# G021Kng.net
KiCad netlist of a schematic drawn in EAGLE
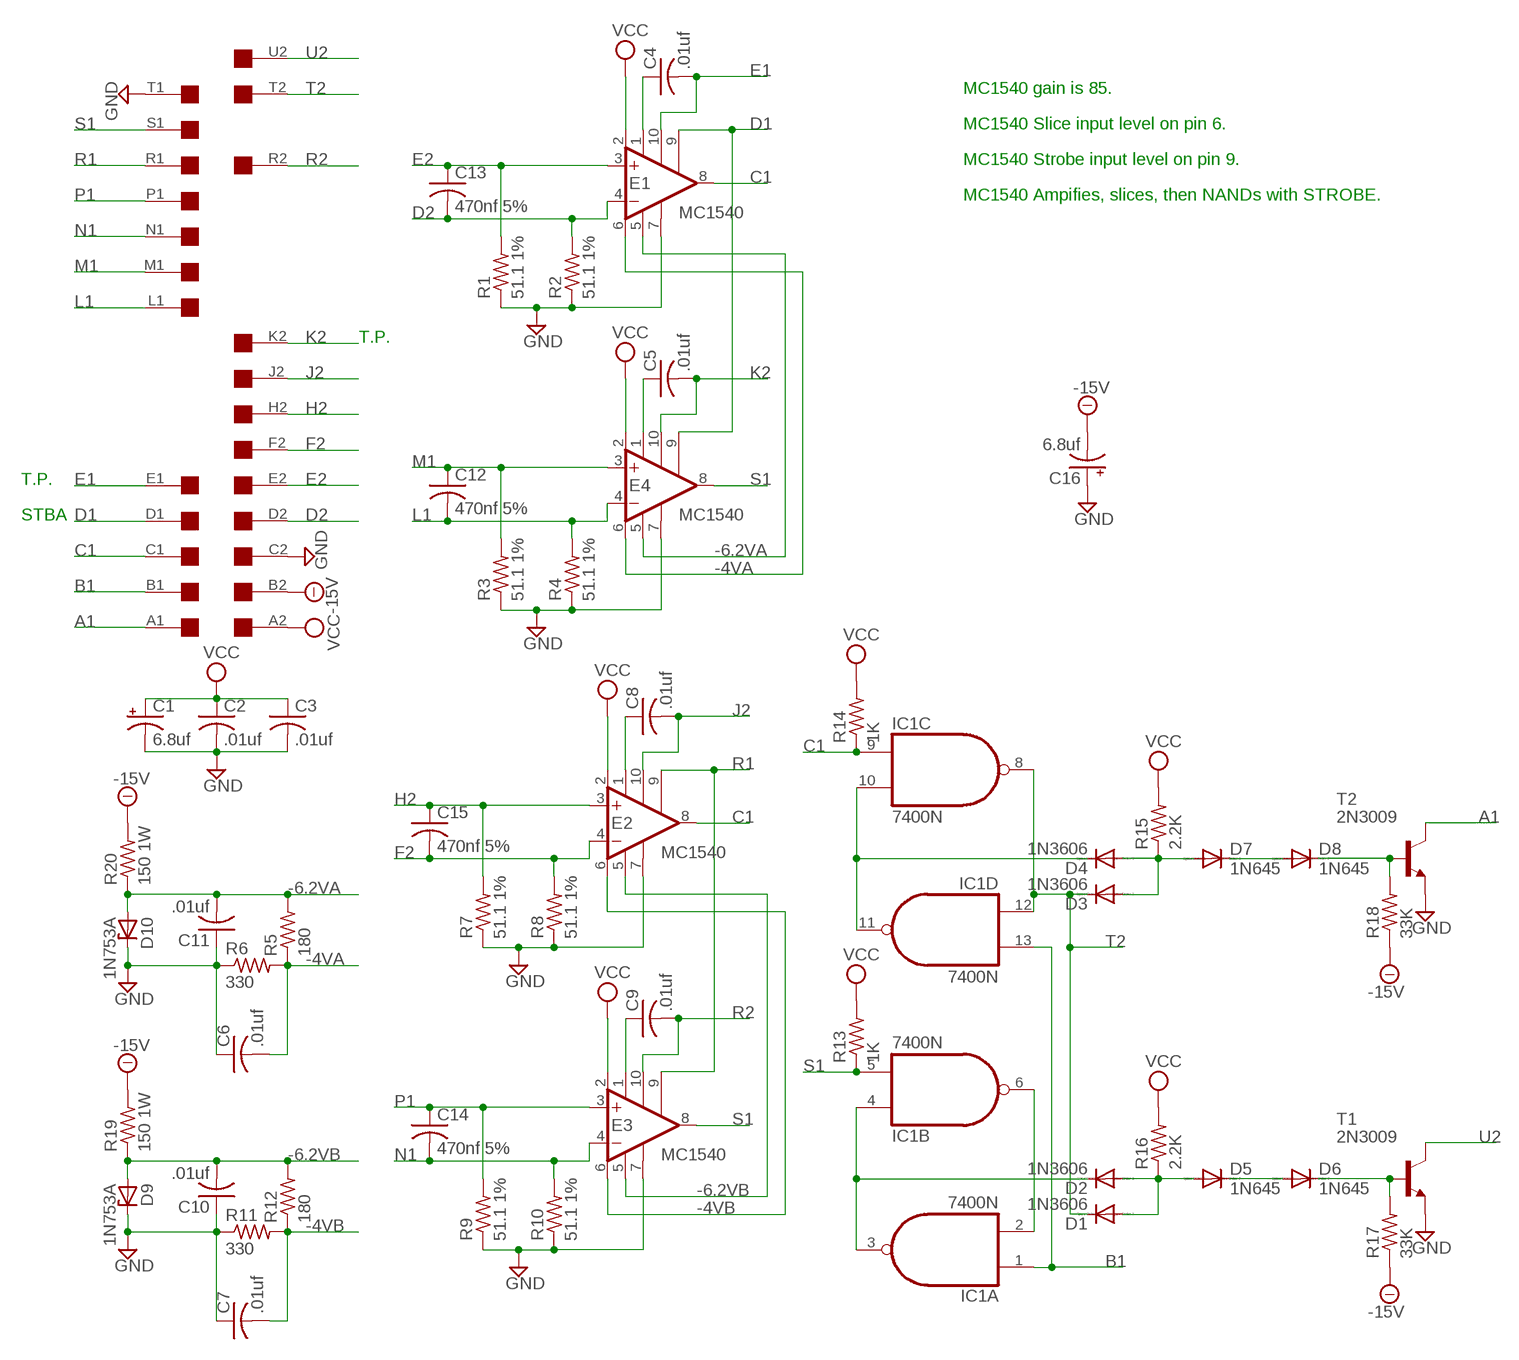
[diagram p0: schematic, sheet 1]

(export (version "E")
  (design (tool "Eeschema 10.0.6"))
  (components
    (comp (ref "C1")
      (value "6.8uf")
      (footprint "eagle-import:E22-6")
      (libsource (lib "eagle-import") (part "CPOL-USE22-6AXIAL"))
    )
    (comp (ref "C2")
      (value ".01uf")
      (footprint "eagle-import:C050-025X075")
      (libsource (lib "eagle-import") (part "C-US050-025X075"))
    )
    (comp (ref "C3")
      (value ".01uf")
      (footprint "eagle-import:C050-025X075")
      (libsource (lib "eagle-import") (part "C-US050-025X075"))
    )
    (comp (ref "C4")
      (value ".01uf")
      (footprint "eagle-import:C050-025X075")
      (libsource (lib "eagle-import") (part "C-US050-025X075"))
    )
    (comp (ref "C5")
      (value ".01uf")
      (footprint "eagle-import:C050-025X075")
      (libsource (lib "eagle-import") (part "C-US050-025X075"))
    )
    (comp (ref "C6")
      (value ".01uf")
      (footprint "eagle-import:C050-025X075")
      (libsource (lib "eagle-import") (part "C-US050-025X075"))
    )
    (comp (ref "C7")
      (value ".01uf")
      (footprint "eagle-import:C050-025X075")
      (libsource (lib "eagle-import") (part "C-US050-025X075"))
    )
    (comp (ref "C8")
      (value ".01uf")
      (footprint "eagle-import:C050-025X075")
      (libsource (lib "eagle-import") (part "C-US050-025X075"))
    )
    (comp (ref "C9")
      (value ".01uf")
      (footprint "eagle-import:C050-025X075")
      (libsource (lib "eagle-import") (part "C-US050-025X075"))
    )
    (comp (ref "C10")
      (value ".01uf")
      (footprint "eagle-import:C050-025X075")
      (libsource (lib "eagle-import") (part "C-US050-025X075"))
    )
    (comp (ref "C11")
      (value ".01uf")
      (footprint "eagle-import:C050-025X075")
      (libsource (lib "eagle-import") (part "C-US050-025X075"))
    )
    (comp (ref "C12")
      (value "470nf 5%")
      (footprint "eagle-import:C050-025X075")
      (libsource (lib "eagle-import") (part "C-US050-025X075"))
    )
    (comp (ref "C13")
      (value "470nf 5%")
      (footprint "eagle-import:C050-025X075")
      (libsource (lib "eagle-import") (part "C-US050-025X075"))
    )
    (comp (ref "C14")
      (value "470nf 5%")
      (footprint "eagle-import:C050-025X075")
      (libsource (lib "eagle-import") (part "C-US050-025X075"))
    )
    (comp (ref "C15")
      (value "470nf 5%")
      (footprint "eagle-import:C050-025X075")
      (libsource (lib "eagle-import") (part "C-US050-025X075"))
    )
    (comp (ref "C16")
      (value "6.8uf")
      (footprint "eagle-import:E22-6")
      (libsource (lib "eagle-import") (part "CPOL-USE22-6AXIAL"))
    )
    (comp (ref "D1")
      (value "1N3606")
      (footprint "eagle-import:DO35-10")
      (libsource (lib "eagle-import") (part "1N4148DO35-10"))
    )
    (comp (ref "D2")
      (value "1N3606")
      (footprint "eagle-import:DO35-10")
      (libsource (lib "eagle-import") (part "1N4148DO35-10"))
    )
    (comp (ref "D3")
      (value "1N3606")
      (footprint "eagle-import:DO35-10")
      (libsource (lib "eagle-import") (part "1N4148DO35-10"))
    )
    (comp (ref "D4")
      (value "1N3606")
      (footprint "eagle-import:DO35-10")
      (libsource (lib "eagle-import") (part "1N4148DO35-10"))
    )
    (comp (ref "D5")
      (value "1N645")
      (footprint "eagle-import:DO35-10")
      (libsource (lib "eagle-import") (part "1N4148DO35-10"))
    )
    (comp (ref "D6")
      (value "1N645")
      (footprint "eagle-import:DO35-10")
      (libsource (lib "eagle-import") (part "1N4148DO35-10"))
    )
    (comp (ref "D7")
      (value "1N645")
      (footprint "eagle-import:DO35-10")
      (libsource (lib "eagle-import") (part "1N4148DO35-10"))
    )
    (comp (ref "D8")
      (value "1N645")
      (footprint "eagle-import:DO35-10")
      (libsource (lib "eagle-import") (part "1N4148DO35-10"))
    )
    (comp (ref "D9")
      (value "1N753A")
      (footprint "eagle-import:F126Z10")
      (libsource (lib "eagle-import") (part "ZENER-DIODEF126-10"))
    )
    (comp (ref "D10")
      (value "1N753A")
      (footprint "eagle-import:F126Z10")
      (libsource (lib "eagle-import") (part "ZENER-DIODEF126-10"))
    )
    (comp (ref "E1")
      (value "MC1540")
      (footprint "eagle-import:602B")
      (libsource (lib "eagle-import") (part "MC1540G"))
    )
    (comp (ref "E2")
      (value "MC1540")
      (footprint "eagle-import:602B")
      (libsource (lib "eagle-import") (part "MC1540G"))
    )
    (comp (ref "E3")
      (value "MC1540")
      (footprint "eagle-import:602B")
      (libsource (lib "eagle-import") (part "MC1540G"))
    )
    (comp (ref "E4")
      (value "MC1540")
      (footprint "eagle-import:602B")
      (libsource (lib "eagle-import") (part "MC1540G"))
    )
    (comp (ref "EDGE")
      (value "EDGE-2ECONO")
      (footprint "eagle-import:ECONOSINGLE")
      (libsource (lib "eagle-import") (part "EDGE-2ECONO"))
    )
    (comp (ref "IC1")
      (value "7400N")
      (footprint "eagle-import:DIL14")
      (libsource (lib "eagle-import") (part "7400N"))
    )
    (comp (ref "R1")
      (value "51.1 1%")
      (footprint "eagle-import:0207_10")
      (libsource (lib "eagle-import") (part "R-US_0207/10"))
    )
    (comp (ref "R2")
      (value "51.1 1%")
      (footprint "eagle-import:0207_10")
      (libsource (lib "eagle-import") (part "R-US_0207/10"))
    )
    (comp (ref "R3")
      (value "51.1 1%")
      (footprint "eagle-import:0207_10")
      (libsource (lib "eagle-import") (part "R-US_0207/10"))
    )
    (comp (ref "R4")
      (value "51.1 1%")
      (footprint "eagle-import:0207_10")
      (libsource (lib "eagle-import") (part "R-US_0207/10"))
    )
    (comp (ref "R5")
      (value "180")
      (footprint "eagle-import:0207_10")
      (libsource (lib "eagle-import") (part "R-US_0207/10"))
    )
    (comp (ref "R6")
      (value "330")
      (footprint "eagle-import:0207_10")
      (libsource (lib "eagle-import") (part "R-US_0207/10"))
    )
    (comp (ref "R7")
      (value "51.1 1%")
      (footprint "eagle-import:0207_10")
      (libsource (lib "eagle-import") (part "R-US_0207/10"))
    )
    (comp (ref "R8")
      (value "51.1 1%")
      (footprint "eagle-import:0207_10")
      (libsource (lib "eagle-import") (part "R-US_0207/10"))
    )
    (comp (ref "R9")
      (value "51.1 1%")
      (footprint "eagle-import:0207_10")
      (libsource (lib "eagle-import") (part "R-US_0207/10"))
    )
    (comp (ref "R10")
      (value "51.1 1%")
      (footprint "eagle-import:0207_10")
      (libsource (lib "eagle-import") (part "R-US_0207/10"))
    )
    (comp (ref "R11")
      (value "330")
      (footprint "eagle-import:0207_10")
      (libsource (lib "eagle-import") (part "R-US_0207/10"))
    )
    (comp (ref "R12")
      (value "180")
      (footprint "eagle-import:0207_10")
      (libsource (lib "eagle-import") (part "R-US_0207/10"))
    )
    (comp (ref "R13")
      (value "1K")
      (footprint "eagle-import:0207_10")
      (libsource (lib "eagle-import") (part "R-US_0207/10"))
    )
    (comp (ref "R14")
      (value "1K")
      (footprint "eagle-import:0207_10")
      (libsource (lib "eagle-import") (part "R-US_0207/10"))
    )
    (comp (ref "R15")
      (value "2.2K")
      (footprint "eagle-import:0207_10")
      (libsource (lib "eagle-import") (part "R-US_0207/10"))
    )
    (comp (ref "R16")
      (value "2.2K")
      (footprint "eagle-import:0207_10")
      (libsource (lib "eagle-import") (part "R-US_0207/10"))
    )
    (comp (ref "R17")
      (value "33K")
      (footprint "eagle-import:0207_10")
      (libsource (lib "eagle-import") (part "R-US_0207/10"))
    )
    (comp (ref "R18")
      (value "33K")
      (footprint "eagle-import:0207_10")
      (libsource (lib "eagle-import") (part "R-US_0207/10"))
    )
    (comp (ref "R19")
      (value "150 1W")
      (footprint "eagle-import:0414_15")
      (libsource (lib "eagle-import") (part "R-US_0414/15"))
    )
    (comp (ref "R20")
      (value "150 1W")
      (footprint "eagle-import:0414_15")
      (libsource (lib "eagle-import") (part "R-US_0414/15"))
    )
    (comp (ref "T1")
      (value "2N3009")
      (footprint "eagle-import:TO92")
      (libsource (lib "eagle-import") (part "2N3565"))
    )
    (comp (ref "T2")
      (value "2N3009")
      (footprint "eagle-import:TO92")
      (libsource (lib "eagle-import") (part "2N3565"))
    )
  )
  (nets
    (net (code "1") (name "-15V") (class "Default")
      (node (ref "C16") (pin "-") (pinfunction "-_-") (pintype "passive"))
      (node (ref "EDGE") (pin "B2") (pinfunction "1_B2") (pintype "bidirectional"))
      (node (ref "R17") (pin "1") (pinfunction "1_1") (pintype "passive"))
      (node (ref "R18") (pin "1") (pinfunction "1_1") (pintype "passive"))
      (node (ref "R19") (pin "2") (pinfunction "2_2") (pintype "passive"))
      (node (ref "R20") (pin "2") (pinfunction "2_2") (pintype "passive"))
    )
    (net (code "2") (name "/-4VA") (class "Default")
      (node (ref "C6") (pin "2") (pinfunction "2_2") (pintype "passive"))
      (node (ref "E1") (pin "6") (pinfunction "SLICE_6") (pintype "bidirectional"))
      (node (ref "E4") (pin "6") (pinfunction "SLICE_6") (pintype "bidirectional"))
      (node (ref "R5") (pin "1") (pinfunction "1_1") (pintype "passive"))
      (node (ref "R6") (pin "2") (pinfunction "2_2") (pintype "passive"))
    )
    (net (code "3") (name "/-4VB") (class "Default")
      (node (ref "C7") (pin "2") (pinfunction "2_2") (pintype "passive"))
      (node (ref "E2") (pin "6") (pinfunction "SLICE_6") (pintype "bidirectional"))
      (node (ref "E3") (pin "6") (pinfunction "SLICE_6") (pintype "bidirectional"))
      (node (ref "R11") (pin "2") (pinfunction "2_2") (pintype "passive"))
      (node (ref "R12") (pin "1") (pinfunction "1_1") (pintype "passive"))
    )
    (net (code "4") (name "/-6.2VA") (class "Default")
      (node (ref "C11") (pin "2") (pinfunction "2_2") (pintype "passive"))
      (node (ref "D10") (pin "A") (pinfunction "A_A") (pintype "passive"))
      (node (ref "E1") (pin "5") (pinfunction "V-_5") (pintype "power_in"))
      (node (ref "E4") (pin "5") (pinfunction "V-_5") (pintype "power_in"))
      (node (ref "R20") (pin "1") (pinfunction "1_1") (pintype "passive"))
      (node (ref "R5") (pin "2") (pinfunction "2_2") (pintype "passive"))
    )
    (net (code "5") (name "/-6.2VB") (class "Default")
      (node (ref "C10") (pin "2") (pinfunction "2_2") (pintype "passive"))
      (node (ref "D9") (pin "A") (pinfunction "A_A") (pintype "passive"))
      (node (ref "E2") (pin "5") (pinfunction "V-_5") (pintype "power_in"))
      (node (ref "E3") (pin "5") (pinfunction "V-_5") (pintype "power_in"))
      (node (ref "R12") (pin "2") (pinfunction "2_2") (pintype "passive"))
      (node (ref "R19") (pin "1") (pinfunction "1_1") (pintype "passive"))
    )
    (net (code "6") (name "/A1") (class "Default")
      (node (ref "EDGE") (pin "A1") (pinfunction "1_A1") (pintype "bidirectional"))
      (node (ref "T2") (pin "1") (pinfunction "C_1") (pintype "passive"))
    )
    (net (code "7") (name "/B1") (class "Default")
      (node (ref "EDGE") (pin "B1") (pinfunction "1_B1") (pintype "bidirectional"))
      (node (ref "IC1") (pin "1") (pinfunction "I0_1") (pintype "input"))
      (node (ref "IC1") (pin "13") (pinfunction "I1_13") (pintype "input"))
    )
    (net (code "8") (name "/C1") (class "Default")
      (node (ref "E1") (pin "8") (pinfunction "OUT_8") (pintype "open_collector"))
      (node (ref "E2") (pin "8") (pinfunction "OUT_8") (pintype "open_collector"))
      (node (ref "EDGE") (pin "C1") (pinfunction "1_C1") (pintype "bidirectional"))
      (node (ref "IC1") (pin "9") (pinfunction "I0_9") (pintype "input"))
      (node (ref "R14") (pin "1") (pinfunction "1_1") (pintype "passive"))
    )
    (net (code "9") (name "/D1") (class "Default")
      (node (ref "E1") (pin "9") (pinfunction "ISTROBE_9") (pintype "passive"))
      (node (ref "E4") (pin "9") (pinfunction "ISTROBE_9") (pintype "passive"))
      (node (ref "EDGE") (pin "D1") (pinfunction "1_D1") (pintype "bidirectional"))
    )
    (net (code "10") (name "/D2") (class "Default")
      (node (ref "C13") (pin "2") (pinfunction "2_2") (pintype "passive"))
      (node (ref "E1") (pin "4") (pinfunction "-IN_4") (pintype "input"))
      (node (ref "EDGE") (pin "D2") (pinfunction "1_D2") (pintype "bidirectional"))
      (node (ref "R2") (pin "2") (pinfunction "2_2") (pintype "passive"))
    )
    (net (code "11") (name "/E1") (class "Default")
      (node (ref "C4") (pin "2") (pinfunction "2_2") (pintype "passive"))
      (node (ref "E1") (pin "10") (pinfunction "CEXTB_10") (pintype "passive"))
      (node (ref "EDGE") (pin "E1") (pinfunction "1_E1") (pintype "bidirectional"))
    )
    (net (code "12") (name "/E2") (class "Default")
      (node (ref "C13") (pin "1") (pinfunction "1_1") (pintype "passive"))
      (node (ref "E1") (pin "3") (pinfunction "+IN_3") (pintype "input"))
      (node (ref "EDGE") (pin "E2") (pinfunction "1_E2") (pintype "bidirectional"))
      (node (ref "R1") (pin "2") (pinfunction "2_2") (pintype "passive"))
    )
    (net (code "13") (name "/F2") (class "Default")
      (node (ref "C15") (pin "2") (pinfunction "2_2") (pintype "passive"))
      (node (ref "E2") (pin "4") (pinfunction "-IN_4") (pintype "input"))
      (node (ref "EDGE") (pin "F2") (pinfunction "1_F2") (pintype "bidirectional"))
      (node (ref "R8") (pin "2") (pinfunction "2_2") (pintype "passive"))
    )
    (net (code "14") (name "/H2") (class "Default")
      (node (ref "C15") (pin "1") (pinfunction "1_1") (pintype "passive"))
      (node (ref "E2") (pin "3") (pinfunction "+IN_3") (pintype "input"))
      (node (ref "EDGE") (pin "H2") (pinfunction "1_H2") (pintype "bidirectional"))
      (node (ref "R7") (pin "2") (pinfunction "2_2") (pintype "passive"))
    )
    (net (code "15") (name "/J2") (class "Default")
      (node (ref "C8") (pin "2") (pinfunction "2_2") (pintype "passive"))
      (node (ref "E2") (pin "10") (pinfunction "CEXTB_10") (pintype "passive"))
      (node (ref "EDGE") (pin "J2") (pinfunction "1_J2") (pintype "bidirectional"))
    )
    (net (code "16") (name "/K2") (class "Default")
      (node (ref "C5") (pin "2") (pinfunction "2_2") (pintype "passive"))
      (node (ref "E4") (pin "10") (pinfunction "CEXTB_10") (pintype "passive"))
      (node (ref "EDGE") (pin "K2") (pinfunction "1_K2") (pintype "bidirectional"))
    )
    (net (code "17") (name "/L1") (class "Default")
      (node (ref "C12") (pin "2") (pinfunction "2_2") (pintype "passive"))
      (node (ref "E4") (pin "4") (pinfunction "-IN_4") (pintype "input"))
      (node (ref "EDGE") (pin "L1") (pinfunction "1_L1") (pintype "bidirectional"))
      (node (ref "R4") (pin "2") (pinfunction "2_2") (pintype "passive"))
    )
    (net (code "18") (name "/M1") (class "Default")
      (node (ref "C12") (pin "1") (pinfunction "1_1") (pintype "passive"))
      (node (ref "E4") (pin "3") (pinfunction "+IN_3") (pintype "input"))
      (node (ref "EDGE") (pin "M1") (pinfunction "1_M1") (pintype "bidirectional"))
      (node (ref "R3") (pin "2") (pinfunction "2_2") (pintype "passive"))
    )
    (net (code "19") (name "/N1") (class "Default")
      (node (ref "C14") (pin "2") (pinfunction "2_2") (pintype "passive"))
      (node (ref "E3") (pin "4") (pinfunction "-IN_4") (pintype "input"))
      (node (ref "EDGE") (pin "N1") (pinfunction "1_N1") (pintype "bidirectional"))
      (node (ref "R10") (pin "2") (pinfunction "2_2") (pintype "passive"))
    )
    (net (code "20") (name "/P1") (class "Default")
      (node (ref "C14") (pin "1") (pinfunction "1_1") (pintype "passive"))
      (node (ref "E3") (pin "3") (pinfunction "+IN_3") (pintype "input"))
      (node (ref "EDGE") (pin "P1") (pinfunction "1_P1") (pintype "bidirectional"))
      (node (ref "R9") (pin "2") (pinfunction "2_2") (pintype "passive"))
    )
    (net (code "21") (name "/R1") (class "Default")
      (node (ref "E2") (pin "9") (pinfunction "ISTROBE_9") (pintype "passive"))
      (node (ref "E3") (pin "9") (pinfunction "ISTROBE_9") (pintype "passive"))
      (node (ref "EDGE") (pin "R1") (pinfunction "1_R1") (pintype "bidirectional"))
    )
    (net (code "22") (name "/R2") (class "Default")
      (node (ref "C9") (pin "2") (pinfunction "2_2") (pintype "passive"))
      (node (ref "E3") (pin "10") (pinfunction "CEXTB_10") (pintype "passive"))
      (node (ref "EDGE") (pin "R2") (pinfunction "1_R2") (pintype "bidirectional"))
    )
    (net (code "23") (name "/S1") (class "Default")
      (node (ref "E3") (pin "8") (pinfunction "OUT_8") (pintype "open_collector"))
      (node (ref "E4") (pin "8") (pinfunction "OUT_8") (pintype "open_collector"))
      (node (ref "EDGE") (pin "S1") (pinfunction "1_S1") (pintype "bidirectional"))
      (node (ref "IC1") (pin "5") (pinfunction "I1_5") (pintype "input"))
      (node (ref "R13") (pin "1") (pinfunction "1_1") (pintype "passive"))
    )
    (net (code "24") (name "/T2") (class "Default")
      (node (ref "D1") (pin "C") (pinfunction "C_C") (pintype "passive"))
      (node (ref "D3") (pin "C") (pinfunction "C_C") (pintype "passive"))
      (node (ref "EDGE") (pin "T2") (pinfunction "1_T2") (pintype "bidirectional"))
      (node (ref "IC1") (pin "12") (pinfunction "I0_12") (pintype "input"))
      (node (ref "IC1") (pin "8") (pinfunction "O_8") (pintype "output"))
    )
    (net (code "25") (name "/U2") (class "Default")
      (node (ref "EDGE") (pin "U2") (pinfunction "1_U2") (pintype "bidirectional"))
      (node (ref "T1") (pin "1") (pinfunction "C_1") (pintype "passive"))
    )
    (net (code "26") (name "GND") (class "Default")
      (node (ref "C1") (pin "-") (pinfunction "-_-") (pintype "passive"))
      (node (ref "C10") (pin "1") (pinfunction "1_1") (pintype "passive"))
      (node (ref "C11") (pin "1") (pinfunction "1_1") (pintype "passive"))
      (node (ref "C16") (pin "+") (pinfunction "+_+") (pintype "passive"))
      (node (ref "C2") (pin "2") (pinfunction "2_2") (pintype "passive"))
      (node (ref "C3") (pin "2") (pinfunction "2_2") (pintype "passive"))
      (node (ref "C6") (pin "1") (pinfunction "1_1") (pintype "passive"))
      (node (ref "C7") (pin "1") (pinfunction "1_1") (pintype "passive"))
      (node (ref "D10") (pin "C") (pinfunction "C_C") (pintype "passive"))
      (node (ref "D9") (pin "C") (pinfunction "C_C") (pintype "passive"))
      (node (ref "E1") (pin "7") (pinfunction "GND_7") (pintype "power_in"))
      (node (ref "E2") (pin "7") (pinfunction "GND_7") (pintype "power_in"))
      (node (ref "E3") (pin "7") (pinfunction "GND_7") (pintype "power_in"))
      (node (ref "E4") (pin "7") (pinfunction "GND_7") (pintype "power_in"))
      (node (ref "EDGE") (pin "C2") (pinfunction "1_C2") (pintype "bidirectional"))
      (node (ref "EDGE") (pin "T1") (pinfunction "1_T1") (pintype "bidirectional"))
      (node (ref "R1") (pin "1") (pinfunction "1_1") (pintype "passive"))
      (node (ref "R10") (pin "1") (pinfunction "1_1") (pintype "passive"))
      (node (ref "R11") (pin "1") (pinfunction "1_1") (pintype "passive"))
      (node (ref "R2") (pin "1") (pinfunction "1_1") (pintype "passive"))
      (node (ref "R3") (pin "1") (pinfunction "1_1") (pintype "passive"))
      (node (ref "R4") (pin "1") (pinfunction "1_1") (pintype "passive"))
      (node (ref "R6") (pin "1") (pinfunction "1_1") (pintype "passive"))
      (node (ref "R7") (pin "1") (pinfunction "1_1") (pintype "passive"))
      (node (ref "R8") (pin "1") (pinfunction "1_1") (pintype "passive"))
      (node (ref "R9") (pin "1") (pinfunction "1_1") (pintype "passive"))
      (node (ref "T1") (pin "3") (pinfunction "E_3") (pintype "passive"))
      (node (ref "T2") (pin "3") (pinfunction "E_3") (pintype "passive"))
    )
    (net (code "27") (name "Net-(D1-PadA)") (class "Default")
      (node (ref "D1") (pin "A") (pinfunction "A_A") (pintype "passive"))
      (node (ref "D2") (pin "A") (pinfunction "A_A") (pintype "passive"))
      (node (ref "D5") (pin "A") (pinfunction "A_A") (pintype "passive"))
      (node (ref "R16") (pin "1") (pinfunction "1_1") (pintype "passive"))
    )
    (net (code "28") (name "Net-(D3-PadA)") (class "Default")
      (node (ref "D3") (pin "A") (pinfunction "A_A") (pintype "passive"))
      (node (ref "D4") (pin "A") (pinfunction "A_A") (pintype "passive"))
      (node (ref "D7") (pin "A") (pinfunction "A_A") (pintype "passive"))
      (node (ref "R15") (pin "1") (pinfunction "1_1") (pintype "passive"))
    )
    (net (code "29") (name "Net-(D5-PadC)") (class "Default")
      (node (ref "D5") (pin "C") (pinfunction "C_C") (pintype "passive"))
      (node (ref "D6") (pin "A") (pinfunction "A_A") (pintype "passive"))
    )
    (net (code "30") (name "Net-(D7-PadC)") (class "Default")
      (node (ref "D7") (pin "C") (pinfunction "C_C") (pintype "passive"))
      (node (ref "D8") (pin "A") (pinfunction "A_A") (pintype "passive"))
    )
    (net (code "31") (name "Net-(E1-CEXTA)") (class "Default")
      (node (ref "C4") (pin "1") (pinfunction "1_1") (pintype "passive"))
      (node (ref "E1") (pin "1") (pinfunction "CEXTA_1") (pintype "passive"))
    )
    (net (code "32") (name "Net-(E2-CEXTA)") (class "Default")
      (node (ref "C8") (pin "1") (pinfunction "1_1") (pintype "passive"))
      (node (ref "E2") (pin "1") (pinfunction "CEXTA_1") (pintype "passive"))
    )
    (net (code "33") (name "Net-(E3-CEXTA)") (class "Default")
      (node (ref "C9") (pin "1") (pinfunction "1_1") (pintype "passive"))
      (node (ref "E3") (pin "1") (pinfunction "CEXTA_1") (pintype "passive"))
    )
    (net (code "34") (name "Net-(E4-CEXTA)") (class "Default")
      (node (ref "C5") (pin "1") (pinfunction "1_1") (pintype "passive"))
      (node (ref "E4") (pin "1") (pinfunction "CEXTA_1") (pintype "passive"))
    )
    (net (code "35") (name "Net-(IC1A-I1)") (class "Default")
      (node (ref "IC1") (pin "2") (pinfunction "I1_2") (pintype "input"))
      (node (ref "IC1") (pin "6") (pinfunction "O_6") (pintype "output"))
    )
    (net (code "36") (name "Net-(IC1A-O)") (class "Default")
      (node (ref "D2") (pin "C") (pinfunction "C_C") (pintype "passive"))
      (node (ref "IC1") (pin "3") (pinfunction "O_3") (pintype "output"))
      (node (ref "IC1") (pin "4") (pinfunction "I0_4") (pintype "input"))
    )
    (net (code "37") (name "Net-(IC1C-I1)") (class "Default")
      (node (ref "D4") (pin "C") (pinfunction "C_C") (pintype "passive"))
      (node (ref "IC1") (pin "10") (pinfunction "I1_10") (pintype "input"))
      (node (ref "IC1") (pin "11") (pinfunction "O_11") (pintype "output"))
    )
    (net (code "38") (name "Net-(T1-B)") (class "Default")
      (node (ref "D6") (pin "C") (pinfunction "C_C") (pintype "passive"))
      (node (ref "R17") (pin "2") (pinfunction "2_2") (pintype "passive"))
      (node (ref "T1") (pin "2") (pinfunction "B_2") (pintype "passive"))
    )
    (net (code "39") (name "Net-(T2-B)") (class "Default")
      (node (ref "D8") (pin "C") (pinfunction "C_C") (pintype "passive"))
      (node (ref "R18") (pin "2") (pinfunction "2_2") (pintype "passive"))
      (node (ref "T2") (pin "2") (pinfunction "B_2") (pintype "passive"))
    )
    (net (code "40") (name "VCC") (class "Default")
      (node (ref "C1") (pin "+") (pinfunction "+_+") (pintype "passive"))
      (node (ref "C2") (pin "1") (pinfunction "1_1") (pintype "passive"))
      (node (ref "C3") (pin "1") (pinfunction "1_1") (pintype "passive"))
      (node (ref "E1") (pin "2") (pinfunction "V+_2") (pintype "power_in"))
      (node (ref "E2") (pin "2") (pinfunction "V+_2") (pintype "power_in"))
      (node (ref "E3") (pin "2") (pinfunction "V+_2") (pintype "power_in"))
      (node (ref "E4") (pin "2") (pinfunction "V+_2") (pintype "power_in"))
      (node (ref "EDGE") (pin "A2") (pinfunction "1_A2") (pintype "bidirectional"))
      (node (ref "R13") (pin "2") (pinfunction "2_2") (pintype "passive"))
      (node (ref "R14") (pin "2") (pinfunction "2_2") (pintype "passive"))
      (node (ref "R15") (pin "2") (pinfunction "2_2") (pintype "passive"))
      (node (ref "R16") (pin "2") (pinfunction "2_2") (pintype "passive"))
    )
  )
)
